# MOTOR_DRIVER_CEC.net
KiCad netlist of a schematic drawn in Altium Designer
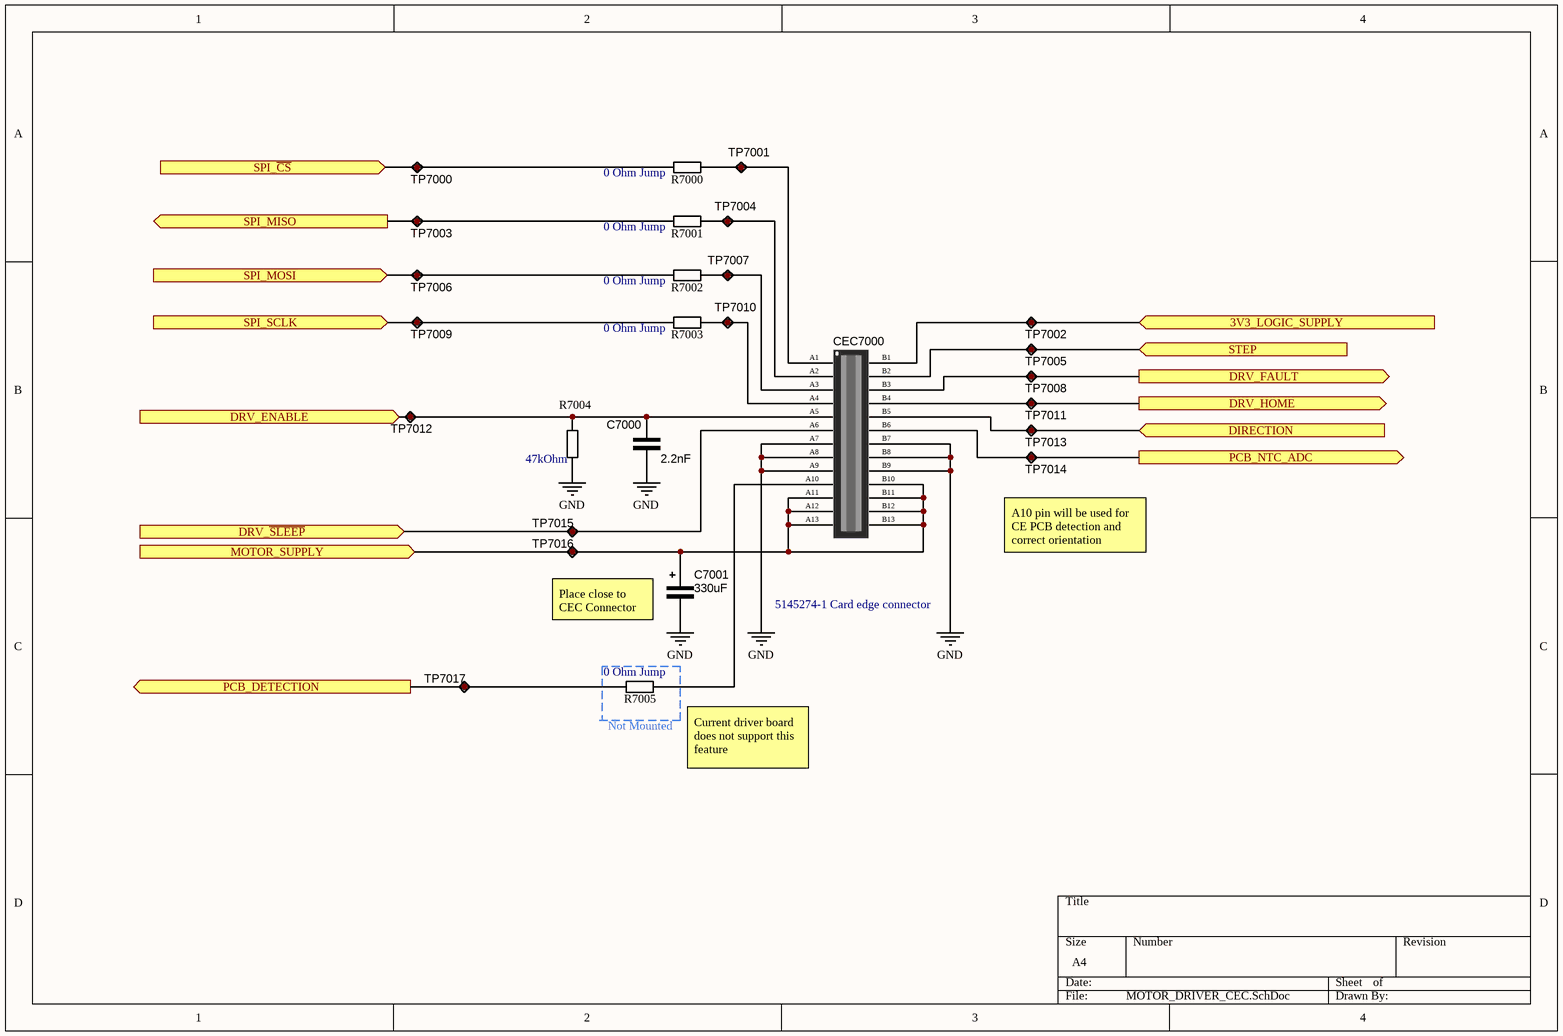
[diagram p0: MOTOR_DRIVER_CEC.SchDoc]

(export (version "E")
  (design (tool "Eeschema 10.0.6"))
  (components
    (comp (ref "C7000")
      (value "2.2nF")
      (footprint "CAP_0603")
      (description "2200 pF ±10% 25V Ceramic Capacitor X7R 0603 (1608 Metric)")
      (fields (field (name "DIGIKEY PART NUMBER") "311-3653-1-ND"))
      (libsource (lib "CapacitorsIntegrated") (part "C000006"))
    )
    (comp (ref "C7001")
      (value "330uF")
      (footprint "CAPAE109103X103M")
      (description "330 µF 50 V Aluminum Electrolytic Capacitors Radial, Can - SMD 120mOhm @ 100kHz 2000 Hrs @ 105°C")
      (fields (field (name "DIGIKEY PART NUMBER") "565-EMZR500ARA331MJA0GCT-ND"))
      (libsource (lib "CapacitorsIntegrated") (part "C000026"))
    )
    (comp (ref "CEC7000")
      (value "5145274-1 Card edge connector")
      (footprint "5145274-1")
      (description "26 Position Female Connector Non Specified - Dual Edge Gold 0.100\" (2.54mm) Black")
      (fields
        (field (name "DIGIKEY PART NUMBER") "5145274-1-ND")
        (field (name "MOUSER PART NUMBER") "571-5145274-1")
      )
      (libsource (lib "ElectroMechanical") (part "00000012"))
    )
    (comp (ref "R7000")
      (value "0 Ohm Jump")
      (footprint "RES_0603")
      (description "0 Ohms Jumper Chip Resistor 0603 (1608 Metric) Automotive AEC-Q200 Thick Film")
      (fields (field (name "DIGIKEY PART NUMBER") "RMCF0603ZT0R00CT-ND"))
      (libsource (lib "ResistorsIntegrated") (part "R000007"))
    )
    (comp (ref "R7001")
      (value "0 Ohm Jump")
      (footprint "RES_0603")
      (description "0 Ohms Jumper Chip Resistor 0603 (1608 Metric) Automotive AEC-Q200 Thick Film")
      (fields (field (name "DIGIKEY PART NUMBER") "RMCF0603ZT0R00CT-ND"))
      (libsource (lib "ResistorsIntegrated") (part "R000007"))
    )
    (comp (ref "R7002")
      (value "0 Ohm Jump")
      (footprint "RES_0603")
      (description "0 Ohms Jumper Chip Resistor 0603 (1608 Metric) Automotive AEC-Q200 Thick Film")
      (fields (field (name "DIGIKEY PART NUMBER") "RMCF0603ZT0R00CT-ND"))
      (libsource (lib "ResistorsIntegrated") (part "R000007"))
    )
    (comp (ref "R7003")
      (value "0 Ohm Jump")
      (footprint "RES_0603")
      (description "0 Ohms Jumper Chip Resistor 0603 (1608 Metric) Automotive AEC-Q200 Thick Film")
      (fields (field (name "DIGIKEY PART NUMBER") "RMCF0603ZT0R00CT-ND"))
      (libsource (lib "ResistorsIntegrated") (part "R000007"))
    )
    (comp (ref "R7004")
      (value "47kOhm")
      (footprint "RES_0603")
      (description "47 kOhms ±1% 0.1W, 1/10W Chip Resistor 0603 (1608 Metric) Moisture Resistant Thick Film")
      (fields (field (name "DIGIKEY PART NUMBER") "311-47.0KHRCT-ND"))
      (libsource (lib "ResistorsIntegrated") (part "R000010"))
    )
    (comp (ref "R7005")
      (value "0 Ohm Jump")
      (footprint "RES_0603")
      (description "0 Ohms Jumper Chip Resistor 0603 (1608 Metric) Automotive AEC-Q200 Thick Film")
      (fields (field (name "DIGIKEY PART NUMBER") "RMCF0603ZT0R00CT-ND"))
      (libsource (lib "ResistorsIntegrated") (part "R000007"))
    )
    (comp (ref "TP7000")
      (value "Test point")
      (footprint "TestPoint")
      (description "Test point 1mm")
      (libsource (lib "IntegratedCircuits") (part "TP002"))
    )
    (comp (ref "TP7001")
      (value "Test point")
      (footprint "TestPoint")
      (description "Test point 1mm")
      (libsource (lib "IntegratedCircuits") (part "TP002"))
    )
    (comp (ref "TP7002")
      (value "Test point")
      (footprint "TestPoint")
      (description "Test point 1mm")
      (libsource (lib "IntegratedCircuits") (part "TP002"))
    )
    (comp (ref "TP7003")
      (value "Test point")
      (footprint "TestPoint")
      (description "Test point 1mm")
      (libsource (lib "IntegratedCircuits") (part "TP002"))
    )
    (comp (ref "TP7004")
      (value "Test point")
      (footprint "TestPoint")
      (description "Test point 1mm")
      (libsource (lib "IntegratedCircuits") (part "TP002"))
    )
    (comp (ref "TP7005")
      (value "Test point")
      (footprint "TestPoint")
      (description "Test point 1mm")
      (libsource (lib "IntegratedCircuits") (part "TP002"))
    )
    (comp (ref "TP7006")
      (value "Test point")
      (footprint "TestPoint")
      (description "Test point 1mm")
      (libsource (lib "IntegratedCircuits") (part "TP002"))
    )
    (comp (ref "TP7007")
      (value "Test point")
      (footprint "TestPoint")
      (description "Test point 1mm")
      (libsource (lib "IntegratedCircuits") (part "TP002"))
    )
    (comp (ref "TP7008")
      (value "Test point")
      (footprint "TestPoint")
      (description "Test point 1mm")
      (libsource (lib "IntegratedCircuits") (part "TP002"))
    )
    (comp (ref "TP7009")
      (value "Test point")
      (footprint "TestPoint")
      (description "Test point 1mm")
      (libsource (lib "IntegratedCircuits") (part "TP002"))
    )
    (comp (ref "TP7010")
      (value "Test point")
      (footprint "TestPoint")
      (description "Test point 1mm")
      (libsource (lib "IntegratedCircuits") (part "TP002"))
    )
    (comp (ref "TP7011")
      (value "Test point")
      (footprint "TestPoint")
      (description "Test point 1mm")
      (libsource (lib "IntegratedCircuits") (part "TP002"))
    )
    (comp (ref "TP7012")
      (value "Test point")
      (footprint "TestPoint")
      (description "Test point 1mm")
      (libsource (lib "IntegratedCircuits") (part "TP002"))
    )
    (comp (ref "TP7013")
      (value "Test point")
      (footprint "TestPoint")
      (description "Test point 1mm")
      (libsource (lib "IntegratedCircuits") (part "TP002"))
    )
    (comp (ref "TP7014")
      (value "Test point")
      (footprint "TestPoint")
      (description "Test point 1mm")
      (libsource (lib "IntegratedCircuits") (part "TP002"))
    )
    (comp (ref "TP7015")
      (value "Test point")
      (footprint "TestPoint")
      (description "Test point 1mm")
      (libsource (lib "IntegratedCircuits") (part "TP002"))
    )
    (comp (ref "TP7016")
      (value "Test point")
      (footprint "TestPoint")
      (description "Test point 1mm")
      (libsource (lib "IntegratedCircuits") (part "TP002"))
    )
    (comp (ref "TP7017")
      (value "Test point")
      (footprint "TestPoint")
      (description "Test point 1mm")
      (libsource (lib "IntegratedCircuits") (part "TP002"))
    )
  )
  (nets
    (net (code "1") (name "/3V3_LOGIC_SUPPLY") (class "Default")
      (node (ref "CEC7000") (pin "B1") (pinfunction "B1_B1") (pintype "passive"))
      (node (ref "TP7002") (pin "1") (pinfunction "1_1") (pintype "passive"))
    )
    (net (code "2") (name "/DIRECTION") (class "Default")
      (node (ref "CEC7000") (pin "B5") (pinfunction "B5_B5") (pintype "passive"))
      (node (ref "TP7013") (pin "1") (pinfunction "1_1") (pintype "passive"))
    )
    (net (code "3") (name "/DRV_ENABLE") (class "Default")
      (node (ref "C7000") (pin "2") (pinfunction "2_2") (pintype "passive"))
      (node (ref "CEC7000") (pin "A5") (pinfunction "A5_A5") (pintype "passive"))
      (node (ref "R7004") (pin "2") (pinfunction "2_2") (pintype "passive"))
      (node (ref "TP7012") (pin "1") (pinfunction "1_1") (pintype "passive"))
    )
    (net (code "4") (name "/DRV_FAULT") (class "Default")
      (node (ref "CEC7000") (pin "B3") (pinfunction "B3_B3") (pintype "passive"))
      (node (ref "TP7008") (pin "1") (pinfunction "1_1") (pintype "passive"))
    )
    (net (code "5") (name "/DRV_HOME") (class "Default")
      (node (ref "CEC7000") (pin "B4") (pinfunction "B4_B4") (pintype "passive"))
      (node (ref "TP7011") (pin "1") (pinfunction "1_1") (pintype "passive"))
    )
    (net (code "6") (name "/DRV_~{SLEEP}") (class "Default")
      (node (ref "CEC7000") (pin "A6") (pinfunction "A6_A6") (pintype "passive"))
      (node (ref "TP7015") (pin "1") (pinfunction "1_1") (pintype "passive"))
    )
    (net (code "7") (name "/MOTOR_SUPPLY") (class "Default")
      (node (ref "C7001") (pin "2") (pinfunction "2_2") (pintype "passive"))
      (node (ref "CEC7000") (pin "A11") (pinfunction "A11_A11") (pintype "passive"))
      (node (ref "CEC7000") (pin "A12") (pinfunction "A12_A12") (pintype "passive"))
      (node (ref "CEC7000") (pin "A13") (pinfunction "A13_A13") (pintype "passive"))
      (node (ref "CEC7000") (pin "B10") (pinfunction "B10_B10") (pintype "passive"))
      (node (ref "CEC7000") (pin "B11") (pinfunction "B11_B11") (pintype "passive"))
      (node (ref "CEC7000") (pin "B12") (pinfunction "B12_B12") (pintype "passive"))
      (node (ref "CEC7000") (pin "B13") (pinfunction "B13_B13") (pintype "passive"))
      (node (ref "TP7016") (pin "1") (pinfunction "1_1") (pintype "passive"))
    )
    (net (code "8") (name "/PCB_DETECTION") (class "Default")
      (node (ref "R7005") (pin "1") (pinfunction "1_1") (pintype "passive"))
      (node (ref "TP7017") (pin "1") (pinfunction "1_1") (pintype "passive"))
    )
    (net (code "9") (name "/PCB_NTC_ADC") (class "Default")
      (node (ref "CEC7000") (pin "B6") (pinfunction "B6_B6") (pintype "passive"))
      (node (ref "TP7014") (pin "1") (pinfunction "1_1") (pintype "passive"))
    )
    (net (code "10") (name "/SPI_MISO") (class "Default")
      (node (ref "R7001") (pin "1") (pinfunction "1_1") (pintype "passive"))
      (node (ref "TP7003") (pin "1") (pinfunction "1_1") (pintype "passive"))
    )
    (net (code "11") (name "/SPI_MOSI") (class "Default")
      (node (ref "R7002") (pin "1") (pinfunction "1_1") (pintype "passive"))
      (node (ref "TP7006") (pin "1") (pinfunction "1_1") (pintype "passive"))
    )
    (net (code "12") (name "/SPI_SCLK") (class "Default")
      (node (ref "R7003") (pin "1") (pinfunction "1_1") (pintype "passive"))
      (node (ref "TP7009") (pin "1") (pinfunction "1_1") (pintype "passive"))
    )
    (net (code "13") (name "/SPI_~{CS}") (class "Default")
      (node (ref "R7000") (pin "1") (pinfunction "1_1") (pintype "passive"))
      (node (ref "TP7000") (pin "1") (pinfunction "1_1") (pintype "passive"))
    )
    (net (code "14") (name "/STEP") (class "Default")
      (node (ref "CEC7000") (pin "B2") (pinfunction "B2_B2") (pintype "passive"))
      (node (ref "TP7005") (pin "1") (pinfunction "1_1") (pintype "passive"))
    )
    (net (code "15") (name "GND") (class "Default")
      (node (ref "C7001") (pin "1") (pinfunction "1_1") (pintype "passive"))
      (node (ref "CEC7000") (pin "A7") (pinfunction "A7_A7") (pintype "passive"))
      (node (ref "CEC7000") (pin "A8") (pinfunction "A8_A8") (pintype "passive"))
      (node (ref "CEC7000") (pin "A9") (pinfunction "A9_A9") (pintype "passive"))
      (node (ref "CEC7000") (pin "B7") (pinfunction "B7_B7") (pintype "passive"))
      (node (ref "CEC7000") (pin "B8") (pinfunction "B8_B8") (pintype "passive"))
      (node (ref "CEC7000") (pin "B9") (pinfunction "B9_B9") (pintype "passive"))
    )
    (net (code "16") (name "Net-(CEC7000-PadA1)") (class "Default")
      (node (ref "CEC7000") (pin "A1") (pinfunction "A1_A1") (pintype "passive"))
      (node (ref "R7000") (pin "2") (pinfunction "2_2") (pintype "passive"))
      (node (ref "TP7001") (pin "1") (pinfunction "1_1") (pintype "passive"))
    )
    (net (code "17") (name "Net-(CEC7000-PadA2)") (class "Default")
      (node (ref "CEC7000") (pin "A2") (pinfunction "A2_A2") (pintype "passive"))
      (node (ref "R7001") (pin "2") (pinfunction "2_2") (pintype "passive"))
      (node (ref "TP7004") (pin "1") (pinfunction "1_1") (pintype "passive"))
    )
    (net (code "18") (name "Net-(CEC7000-PadA3)") (class "Default")
      (node (ref "CEC7000") (pin "A3") (pinfunction "A3_A3") (pintype "passive"))
      (node (ref "R7002") (pin "2") (pinfunction "2_2") (pintype "passive"))
      (node (ref "TP7007") (pin "1") (pinfunction "1_1") (pintype "passive"))
    )
    (net (code "19") (name "Net-(CEC7000-PadA4)") (class "Default")
      (node (ref "CEC7000") (pin "A4") (pinfunction "A4_A4") (pintype "passive"))
      (node (ref "R7003") (pin "2") (pinfunction "2_2") (pintype "passive"))
      (node (ref "TP7010") (pin "1") (pinfunction "1_1") (pintype "passive"))
    )
    (net (code "20") (name "Net-(CEC7000-PadA10)") (class "Default")
      (node (ref "CEC7000") (pin "A10") (pinfunction "A10_A10") (pintype "passive"))
      (node (ref "R7005") (pin "2") (pinfunction "2_2") (pintype "passive"))
    )
    (net (code "21") (name "unconnected-(C7000-Pad1)") (class "Default")
      (node (ref "C7000") (pin "1") (pinfunction "1_1") (pintype "passive"))
    )
    (net (code "22") (name "unconnected-(R7004-Pad1)") (class "Default")
      (node (ref "R7004") (pin "1") (pinfunction "1_1") (pintype "passive"))
    )
  )
)
